# MAIN_MODULE.net
KiCad netlist of a schematic drawn in EAGLE
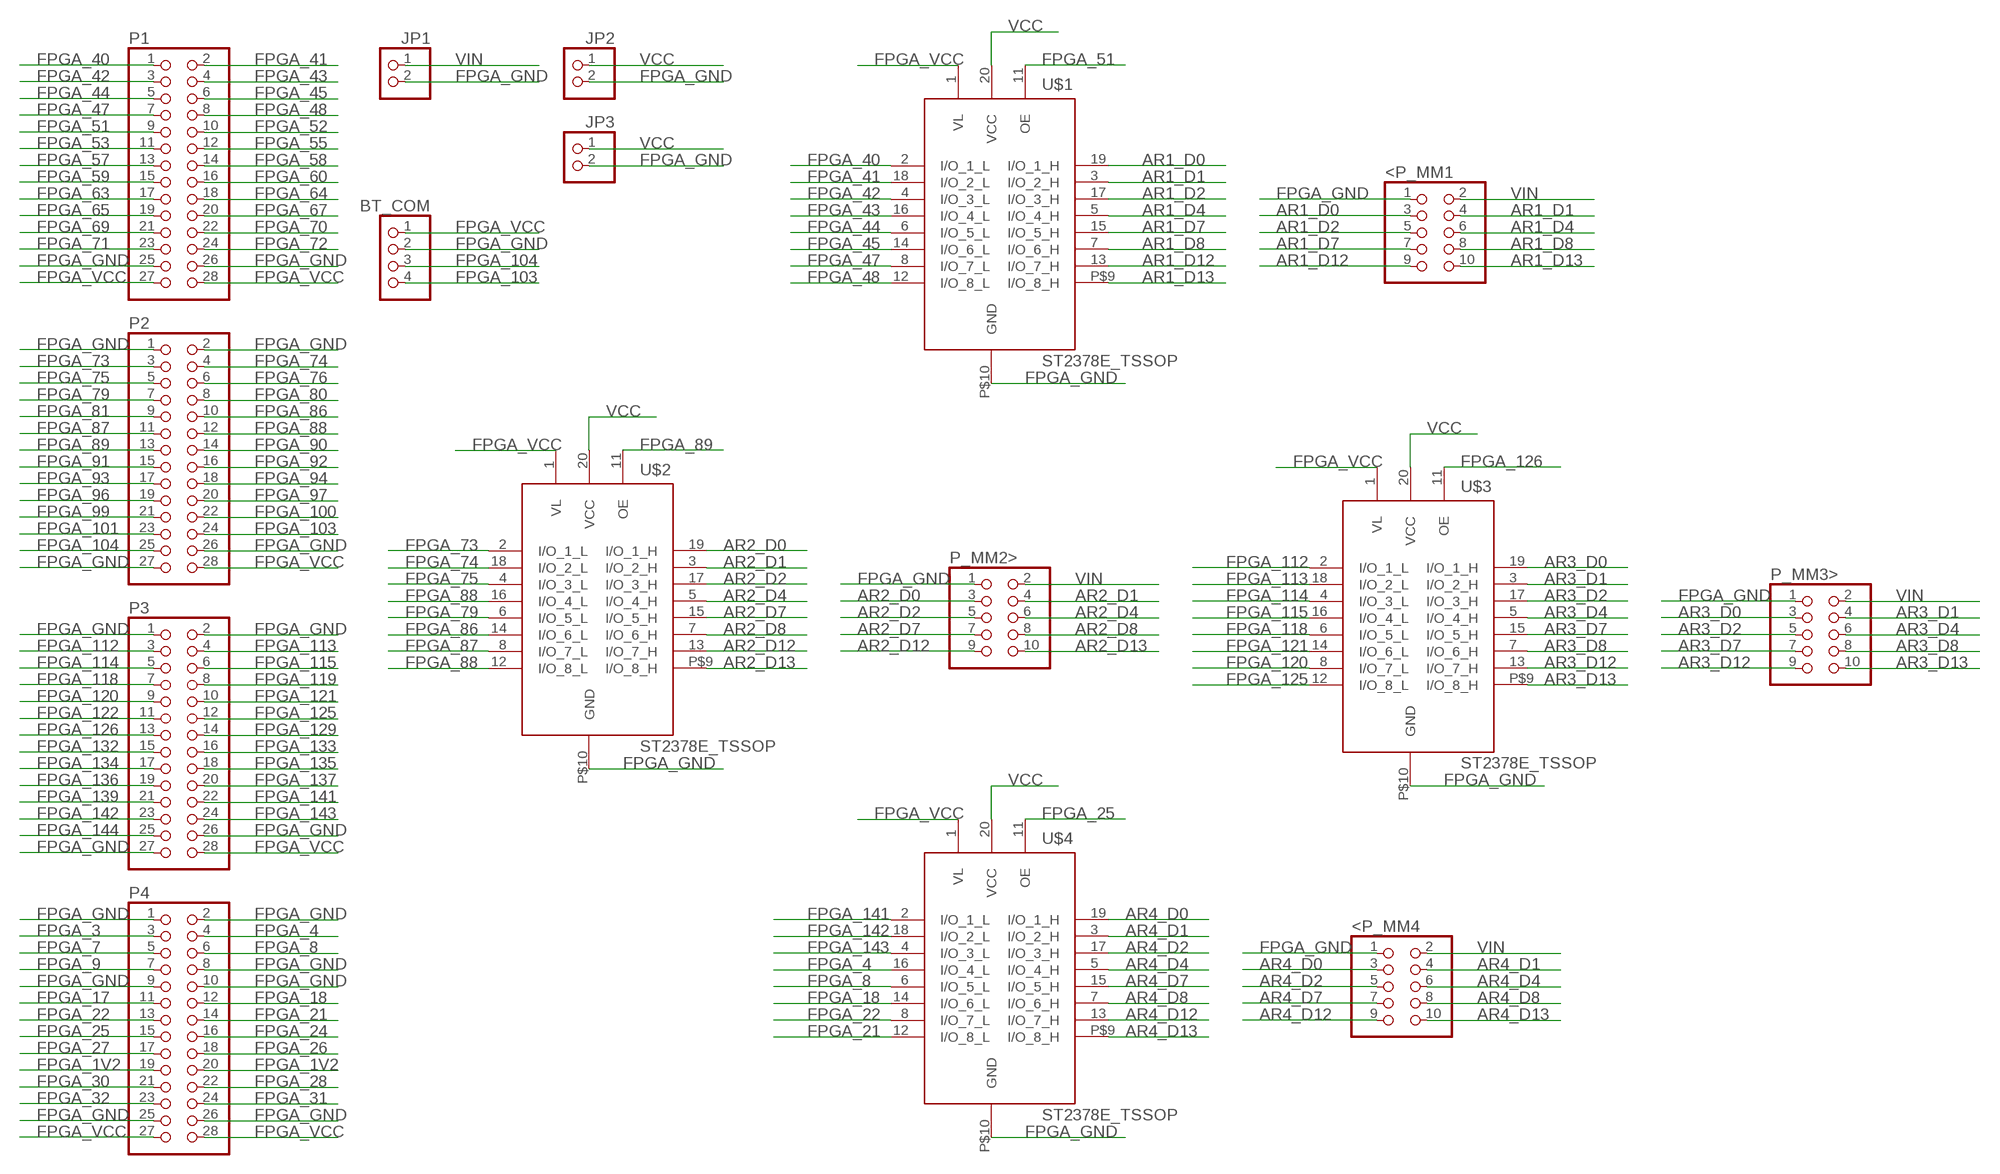
[diagram p0: schematic, sheet 1]

(export (version "E")
  (design (tool "Eeschema 10.0.6"))
  (components
    (comp (ref "<P_MM1")
      (value "PINHD-2X5")
      (footprint "eagle-import:2X05")
      (libsource (lib "eagle-import") (part "PINHD-2X5"))
    )
    (comp (ref "<P_MM4")
      (value "PINHD-2X5")
      (footprint "eagle-import:2X05")
      (libsource (lib "eagle-import") (part "PINHD-2X5"))
    )
    (comp (ref "BT_COM")
      (value "PINHD-1X4")
      (footprint "eagle-import:1X04")
      (libsource (lib "eagle-import") (part "PINHD-1X4"))
    )
    (comp (ref "JP1")
      (value "PINHD-1X2")
      (footprint "eagle-import:1X02")
      (libsource (lib "eagle-import") (part "PINHD-1X2"))
    )
    (comp (ref "JP2")
      (value "PINHD-1X2")
      (footprint "eagle-import:1X02")
      (libsource (lib "eagle-import") (part "PINHD-1X2"))
    )
    (comp (ref "JP3")
      (value "PINHD-1X2")
      (footprint "eagle-import:1X02")
      (libsource (lib "eagle-import") (part "PINHD-1X2"))
    )
    (comp (ref "P1")
      (value "PINHD-2X14")
      (footprint "eagle-import:2X14")
      (libsource (lib "eagle-import") (part "PINHD-2X14"))
    )
    (comp (ref "P2")
      (value "PINHD-2X14")
      (footprint "eagle-import:2X14")
      (libsource (lib "eagle-import") (part "PINHD-2X14"))
    )
    (comp (ref "P3")
      (value "PINHD-2X14")
      (footprint "eagle-import:2X14")
      (libsource (lib "eagle-import") (part "PINHD-2X14"))
    )
    (comp (ref "P4")
      (value "PINHD-2X14")
      (footprint "eagle-import:2X14")
      (libsource (lib "eagle-import") (part "PINHD-2X14"))
    )
    (comp (ref "P_MM2>")
      (value "PINHD-2X5")
      (footprint "eagle-import:2X05")
      (libsource (lib "eagle-import") (part "PINHD-2X5"))
    )
    (comp (ref "P_MM3>")
      (value "PINHD-2X5")
      (footprint "eagle-import:2X05")
      (libsource (lib "eagle-import") (part "PINHD-2X5"))
    )
    (comp (ref "U$1")
      (value "ST2378E_TSSOP")
      (footprint "eagle-import:TSSOP20")
      (libsource (lib "eagle-import") (part "ST2378E_TSSOP"))
    )
    (comp (ref "U$2")
      (value "ST2378E_TSSOP")
      (footprint "eagle-import:TSSOP20")
      (libsource (lib "eagle-import") (part "ST2378E_TSSOP"))
    )
    (comp (ref "U$3")
      (value "ST2378E_TSSOP")
      (footprint "eagle-import:TSSOP20")
      (libsource (lib "eagle-import") (part "ST2378E_TSSOP"))
    )
    (comp (ref "U$4")
      (value "ST2378E_TSSOP")
      (footprint "eagle-import:TSSOP20")
      (libsource (lib "eagle-import") (part "ST2378E_TSSOP"))
    )
  )
  (nets
    (net (code "1") (name "/AR1_D0") (class "Default")
      (node (ref "<P_MM1") (pin "3") (pinfunction "3_3") (pintype "passive"))
      (node (ref "U$1") (pin "19") (pinfunction "I/O_1_H_19") (pintype "bidirectional"))
    )
    (net (code "2") (name "/AR1_D1") (class "Default")
      (node (ref "<P_MM1") (pin "4") (pinfunction "4_4") (pintype "passive"))
      (node (ref "U$1") (pin "3") (pinfunction "I/O_2_H_3") (pintype "bidirectional"))
    )
    (net (code "3") (name "/AR1_D2") (class "Default")
      (node (ref "<P_MM1") (pin "5") (pinfunction "5_5") (pintype "passive"))
      (node (ref "U$1") (pin "17") (pinfunction "I/O_3_H_17") (pintype "bidirectional"))
    )
    (net (code "4") (name "/AR1_D4") (class "Default")
      (node (ref "<P_MM1") (pin "6") (pinfunction "6_6") (pintype "passive"))
      (node (ref "U$1") (pin "5") (pinfunction "I/O_4_H_5") (pintype "bidirectional"))
    )
    (net (code "5") (name "/AR1_D7") (class "Default")
      (node (ref "<P_MM1") (pin "7") (pinfunction "7_7") (pintype "passive"))
      (node (ref "U$1") (pin "15") (pinfunction "I/O_5_H_15") (pintype "bidirectional"))
    )
    (net (code "6") (name "/AR1_D8") (class "Default")
      (node (ref "<P_MM1") (pin "8") (pinfunction "8_8") (pintype "passive"))
      (node (ref "U$1") (pin "7") (pinfunction "I/O_6_H_7") (pintype "bidirectional"))
    )
    (net (code "7") (name "/AR1_D12") (class "Default")
      (node (ref "<P_MM1") (pin "9") (pinfunction "9_9") (pintype "passive"))
      (node (ref "U$1") (pin "13") (pinfunction "I/O_7_H_13") (pintype "bidirectional"))
    )
    (net (code "8") (name "/AR1_D13") (class "Default")
      (node (ref "<P_MM1") (pin "10") (pinfunction "10_10") (pintype "passive"))
      (node (ref "U$1") (pin "P$9") (pinfunction "I/O_8_H_P$9") (pintype "bidirectional"))
    )
    (net (code "9") (name "/AR2_D0") (class "Default")
      (node (ref "P_MM2>") (pin "3") (pinfunction "3_3") (pintype "passive"))
      (node (ref "U$2") (pin "19") (pinfunction "I/O_1_H_19") (pintype "bidirectional"))
    )
    (net (code "10") (name "/AR2_D1") (class "Default")
      (node (ref "P_MM2>") (pin "4") (pinfunction "4_4") (pintype "passive"))
      (node (ref "U$2") (pin "3") (pinfunction "I/O_2_H_3") (pintype "bidirectional"))
    )
    (net (code "11") (name "/AR2_D2") (class "Default")
      (node (ref "P_MM2>") (pin "5") (pinfunction "5_5") (pintype "passive"))
      (node (ref "U$2") (pin "17") (pinfunction "I/O_3_H_17") (pintype "bidirectional"))
    )
    (net (code "12") (name "/AR2_D4") (class "Default")
      (node (ref "P_MM2>") (pin "6") (pinfunction "6_6") (pintype "passive"))
      (node (ref "U$2") (pin "5") (pinfunction "I/O_4_H_5") (pintype "bidirectional"))
    )
    (net (code "13") (name "/AR2_D7") (class "Default")
      (node (ref "P_MM2>") (pin "7") (pinfunction "7_7") (pintype "passive"))
      (node (ref "U$2") (pin "15") (pinfunction "I/O_5_H_15") (pintype "bidirectional"))
    )
    (net (code "14") (name "/AR2_D8") (class "Default")
      (node (ref "P_MM2>") (pin "8") (pinfunction "8_8") (pintype "passive"))
      (node (ref "U$2") (pin "7") (pinfunction "I/O_6_H_7") (pintype "bidirectional"))
    )
    (net (code "15") (name "/AR2_D12") (class "Default")
      (node (ref "P_MM2>") (pin "9") (pinfunction "9_9") (pintype "passive"))
      (node (ref "U$2") (pin "13") (pinfunction "I/O_7_H_13") (pintype "bidirectional"))
    )
    (net (code "16") (name "/AR2_D13") (class "Default")
      (node (ref "P_MM2>") (pin "10") (pinfunction "10_10") (pintype "passive"))
      (node (ref "U$2") (pin "P$9") (pinfunction "I/O_8_H_P$9") (pintype "bidirectional"))
    )
    (net (code "17") (name "/AR3_D0") (class "Default")
      (node (ref "P_MM3>") (pin "3") (pinfunction "3_3") (pintype "passive"))
      (node (ref "U$3") (pin "19") (pinfunction "I/O_1_H_19") (pintype "bidirectional"))
    )
    (net (code "18") (name "/AR3_D1") (class "Default")
      (node (ref "P_MM3>") (pin "4") (pinfunction "4_4") (pintype "passive"))
      (node (ref "U$3") (pin "3") (pinfunction "I/O_2_H_3") (pintype "bidirectional"))
    )
    (net (code "19") (name "/AR3_D2") (class "Default")
      (node (ref "P_MM3>") (pin "5") (pinfunction "5_5") (pintype "passive"))
      (node (ref "U$3") (pin "17") (pinfunction "I/O_3_H_17") (pintype "bidirectional"))
    )
    (net (code "20") (name "/AR3_D4") (class "Default")
      (node (ref "P_MM3>") (pin "6") (pinfunction "6_6") (pintype "passive"))
      (node (ref "U$3") (pin "5") (pinfunction "I/O_4_H_5") (pintype "bidirectional"))
    )
    (net (code "21") (name "/AR3_D7") (class "Default")
      (node (ref "P_MM3>") (pin "7") (pinfunction "7_7") (pintype "passive"))
      (node (ref "U$3") (pin "15") (pinfunction "I/O_5_H_15") (pintype "bidirectional"))
    )
    (net (code "22") (name "/AR3_D8") (class "Default")
      (node (ref "P_MM3>") (pin "8") (pinfunction "8_8") (pintype "passive"))
      (node (ref "U$3") (pin "7") (pinfunction "I/O_6_H_7") (pintype "bidirectional"))
    )
    (net (code "23") (name "/AR3_D12") (class "Default")
      (node (ref "P_MM3>") (pin "9") (pinfunction "9_9") (pintype "passive"))
      (node (ref "U$3") (pin "13") (pinfunction "I/O_7_H_13") (pintype "bidirectional"))
    )
    (net (code "24") (name "/AR3_D13") (class "Default")
      (node (ref "P_MM3>") (pin "10") (pinfunction "10_10") (pintype "passive"))
      (node (ref "U$3") (pin "P$9") (pinfunction "I/O_8_H_P$9") (pintype "bidirectional"))
    )
    (net (code "25") (name "/AR4_D0") (class "Default")
      (node (ref "<P_MM4") (pin "3") (pinfunction "3_3") (pintype "passive"))
      (node (ref "U$4") (pin "19") (pinfunction "I/O_1_H_19") (pintype "bidirectional"))
    )
    (net (code "26") (name "/AR4_D1") (class "Default")
      (node (ref "<P_MM4") (pin "4") (pinfunction "4_4") (pintype "passive"))
      (node (ref "U$4") (pin "3") (pinfunction "I/O_2_H_3") (pintype "bidirectional"))
    )
    (net (code "27") (name "/AR4_D2") (class "Default")
      (node (ref "<P_MM4") (pin "5") (pinfunction "5_5") (pintype "passive"))
      (node (ref "U$4") (pin "17") (pinfunction "I/O_3_H_17") (pintype "bidirectional"))
    )
    (net (code "28") (name "/AR4_D4") (class "Default")
      (node (ref "<P_MM4") (pin "6") (pinfunction "6_6") (pintype "passive"))
      (node (ref "U$4") (pin "5") (pinfunction "I/O_4_H_5") (pintype "bidirectional"))
    )
    (net (code "29") (name "/AR4_D7") (class "Default")
      (node (ref "<P_MM4") (pin "7") (pinfunction "7_7") (pintype "passive"))
      (node (ref "U$4") (pin "15") (pinfunction "I/O_5_H_15") (pintype "bidirectional"))
    )
    (net (code "30") (name "/AR4_D8") (class "Default")
      (node (ref "<P_MM4") (pin "8") (pinfunction "8_8") (pintype "passive"))
      (node (ref "U$4") (pin "7") (pinfunction "I/O_6_H_7") (pintype "bidirectional"))
    )
    (net (code "31") (name "/AR4_D12") (class "Default")
      (node (ref "<P_MM4") (pin "9") (pinfunction "9_9") (pintype "passive"))
      (node (ref "U$4") (pin "13") (pinfunction "I/O_7_H_13") (pintype "bidirectional"))
    )
    (net (code "32") (name "/AR4_D13") (class "Default")
      (node (ref "<P_MM4") (pin "10") (pinfunction "10_10") (pintype "passive"))
      (node (ref "U$4") (pin "P$9") (pinfunction "I/O_8_H_P$9") (pintype "bidirectional"))
    )
    (net (code "33") (name "/FPGA_1V2") (class "Default")
      (node (ref "P4") (pin "19") (pinfunction "19_19") (pintype "passive"))
      (node (ref "P4") (pin "20") (pinfunction "20_20") (pintype "passive"))
    )
    (net (code "34") (name "/FPGA_3") (class "Default")
      (node (ref "P4") (pin "3") (pinfunction "3_3") (pintype "passive"))
    )
    (net (code "35") (name "/FPGA_4") (class "Default")
      (node (ref "P4") (pin "4") (pinfunction "4_4") (pintype "passive"))
      (node (ref "U$4") (pin "16") (pinfunction "I/O_4_L_16") (pintype "bidirectional"))
    )
    (net (code "36") (name "/FPGA_7") (class "Default")
      (node (ref "P4") (pin "5") (pinfunction "5_5") (pintype "passive"))
    )
    (net (code "37") (name "/FPGA_8") (class "Default")
      (node (ref "P4") (pin "6") (pinfunction "6_6") (pintype "passive"))
      (node (ref "U$4") (pin "6") (pinfunction "I/O_5_L_6") (pintype "bidirectional"))
    )
    (net (code "38") (name "/FPGA_9") (class "Default")
      (node (ref "P4") (pin "7") (pinfunction "7_7") (pintype "passive"))
    )
    (net (code "39") (name "/FPGA_17") (class "Default")
      (node (ref "P4") (pin "11") (pinfunction "11_11") (pintype "passive"))
    )
    (net (code "40") (name "/FPGA_18") (class "Default")
      (node (ref "P4") (pin "12") (pinfunction "12_12") (pintype "passive"))
      (node (ref "U$4") (pin "14") (pinfunction "I/O_6_L_14") (pintype "bidirectional"))
    )
    (net (code "41") (name "/FPGA_21") (class "Default")
      (node (ref "P4") (pin "14") (pinfunction "14_14") (pintype "passive"))
      (node (ref "U$4") (pin "12") (pinfunction "I/O_8_L_12") (pintype "bidirectional"))
    )
    (net (code "42") (name "/FPGA_22") (class "Default")
      (node (ref "P4") (pin "13") (pinfunction "13_13") (pintype "passive"))
      (node (ref "U$4") (pin "8") (pinfunction "I/O_7_L_8") (pintype "bidirectional"))
    )
    (net (code "43") (name "/FPGA_24") (class "Default")
      (node (ref "P4") (pin "16") (pinfunction "16_16") (pintype "passive"))
    )
    (net (code "44") (name "/FPGA_25") (class "Default")
      (node (ref "P4") (pin "15") (pinfunction "15_15") (pintype "passive"))
      (node (ref "U$4") (pin "11") (pinfunction "OE_11") (pintype "bidirectional"))
    )
    (net (code "45") (name "/FPGA_26") (class "Default")
      (node (ref "P4") (pin "18") (pinfunction "18_18") (pintype "passive"))
    )
    (net (code "46") (name "/FPGA_27") (class "Default")
      (node (ref "P4") (pin "17") (pinfunction "17_17") (pintype "passive"))
    )
    (net (code "47") (name "/FPGA_28") (class "Default")
      (node (ref "P4") (pin "22") (pinfunction "22_22") (pintype "passive"))
    )
    (net (code "48") (name "/FPGA_30") (class "Default")
      (node (ref "P4") (pin "21") (pinfunction "21_21") (pintype "passive"))
    )
    (net (code "49") (name "/FPGA_31") (class "Default")
      (node (ref "P4") (pin "24") (pinfunction "24_24") (pintype "passive"))
    )
    (net (code "50") (name "/FPGA_32") (class "Default")
      (node (ref "P4") (pin "23") (pinfunction "23_23") (pintype "passive"))
    )
    (net (code "51") (name "/FPGA_40") (class "Default")
      (node (ref "P1") (pin "1") (pinfunction "1_1") (pintype "passive"))
      (node (ref "U$1") (pin "2") (pinfunction "I/O_1_L_2") (pintype "bidirectional"))
    )
    (net (code "52") (name "/FPGA_41") (class "Default")
      (node (ref "P1") (pin "2") (pinfunction "2_2") (pintype "passive"))
      (node (ref "U$1") (pin "18") (pinfunction "I/O_2_L_18") (pintype "bidirectional"))
    )
    (net (code "53") (name "/FPGA_42") (class "Default")
      (node (ref "P1") (pin "3") (pinfunction "3_3") (pintype "passive"))
      (node (ref "U$1") (pin "4") (pinfunction "I/O_3_L_4") (pintype "bidirectional"))
    )
    (net (code "54") (name "/FPGA_43") (class "Default")
      (node (ref "P1") (pin "4") (pinfunction "4_4") (pintype "passive"))
      (node (ref "U$1") (pin "16") (pinfunction "I/O_4_L_16") (pintype "bidirectional"))
    )
    (net (code "55") (name "/FPGA_44") (class "Default")
      (node (ref "P1") (pin "5") (pinfunction "5_5") (pintype "passive"))
      (node (ref "U$1") (pin "6") (pinfunction "I/O_5_L_6") (pintype "bidirectional"))
    )
    (net (code "56") (name "/FPGA_45") (class "Default")
      (node (ref "P1") (pin "6") (pinfunction "6_6") (pintype "passive"))
      (node (ref "U$1") (pin "14") (pinfunction "I/O_6_L_14") (pintype "bidirectional"))
    )
    (net (code "57") (name "/FPGA_47") (class "Default")
      (node (ref "P1") (pin "7") (pinfunction "7_7") (pintype "passive"))
      (node (ref "U$1") (pin "8") (pinfunction "I/O_7_L_8") (pintype "bidirectional"))
    )
    (net (code "58") (name "/FPGA_48") (class "Default")
      (node (ref "P1") (pin "8") (pinfunction "8_8") (pintype "passive"))
      (node (ref "U$1") (pin "12") (pinfunction "I/O_8_L_12") (pintype "bidirectional"))
    )
    (net (code "59") (name "/FPGA_51") (class "Default")
      (node (ref "P1") (pin "9") (pinfunction "9_9") (pintype "passive"))
      (node (ref "U$1") (pin "11") (pinfunction "OE_11") (pintype "bidirectional"))
    )
    (net (code "60") (name "/FPGA_52") (class "Default")
      (node (ref "P1") (pin "10") (pinfunction "10_10") (pintype "passive"))
    )
    (net (code "61") (name "/FPGA_53") (class "Default")
      (node (ref "P1") (pin "11") (pinfunction "11_11") (pintype "passive"))
    )
    (net (code "62") (name "/FPGA_55") (class "Default")
      (node (ref "P1") (pin "12") (pinfunction "12_12") (pintype "passive"))
    )
    (net (code "63") (name "/FPGA_57") (class "Default")
      (node (ref "P1") (pin "13") (pinfunction "13_13") (pintype "passive"))
    )
    (net (code "64") (name "/FPGA_58") (class "Default")
      (node (ref "P1") (pin "14") (pinfunction "14_14") (pintype "passive"))
    )
    (net (code "65") (name "/FPGA_59") (class "Default")
      (node (ref "P1") (pin "15") (pinfunction "15_15") (pintype "passive"))
    )
    (net (code "66") (name "/FPGA_60") (class "Default")
      (node (ref "P1") (pin "16") (pinfunction "16_16") (pintype "passive"))
    )
    (net (code "67") (name "/FPGA_63") (class "Default")
      (node (ref "P1") (pin "17") (pinfunction "17_17") (pintype "passive"))
    )
    (net (code "68") (name "/FPGA_64") (class "Default")
      (node (ref "P1") (pin "18") (pinfunction "18_18") (pintype "passive"))
    )
    (net (code "69") (name "/FPGA_65") (class "Default")
      (node (ref "P1") (pin "19") (pinfunction "19_19") (pintype "passive"))
    )
    (net (code "70") (name "/FPGA_67") (class "Default")
      (node (ref "P1") (pin "20") (pinfunction "20_20") (pintype "passive"))
    )
    (net (code "71") (name "/FPGA_69") (class "Default")
      (node (ref "P1") (pin "21") (pinfunction "21_21") (pintype "passive"))
    )
    (net (code "72") (name "/FPGA_70") (class "Default")
      (node (ref "P1") (pin "22") (pinfunction "22_22") (pintype "passive"))
    )
    (net (code "73") (name "/FPGA_71") (class "Default")
      (node (ref "P1") (pin "23") (pinfunction "23_23") (pintype "passive"))
    )
    (net (code "74") (name "/FPGA_72") (class "Default")
      (node (ref "P1") (pin "24") (pinfunction "24_24") (pintype "passive"))
    )
    (net (code "75") (name "/FPGA_73") (class "Default")
      (node (ref "P2") (pin "3") (pinfunction "3_3") (pintype "passive"))
      (node (ref "U$2") (pin "2") (pinfunction "I/O_1_L_2") (pintype "bidirectional"))
    )
    (net (code "76") (name "/FPGA_74") (class "Default")
      (node (ref "P2") (pin "4") (pinfunction "4_4") (pintype "passive"))
      (node (ref "U$2") (pin "18") (pinfunction "I/O_2_L_18") (pintype "bidirectional"))
    )
    (net (code "77") (name "/FPGA_75") (class "Default")
      (node (ref "P2") (pin "5") (pinfunction "5_5") (pintype "passive"))
      (node (ref "U$2") (pin "4") (pinfunction "I/O_3_L_4") (pintype "bidirectional"))
    )
    (net (code "78") (name "/FPGA_76") (class "Default")
      (node (ref "P2") (pin "6") (pinfunction "6_6") (pintype "passive"))
    )
    (net (code "79") (name "/FPGA_79") (class "Default")
      (node (ref "P2") (pin "7") (pinfunction "7_7") (pintype "passive"))
      (node (ref "U$2") (pin "6") (pinfunction "I/O_5_L_6") (pintype "bidirectional"))
    )
    (net (code "80") (name "/FPGA_80") (class "Default")
      (node (ref "P2") (pin "8") (pinfunction "8_8") (pintype "passive"))
    )
    (net (code "81") (name "/FPGA_81") (class "Default")
      (node (ref "P2") (pin "9") (pinfunction "9_9") (pintype "passive"))
    )
    (net (code "82") (name "/FPGA_86") (class "Default")
      (node (ref "P2") (pin "10") (pinfunction "10_10") (pintype "passive"))
      (node (ref "U$2") (pin "14") (pinfunction "I/O_6_L_14") (pintype "bidirectional"))
    )
    (net (code "83") (name "/FPGA_87") (class "Default")
      (node (ref "P2") (pin "11") (pinfunction "11_11") (pintype "passive"))
      (node (ref "U$2") (pin "8") (pinfunction "I/O_7_L_8") (pintype "bidirectional"))
    )
    (net (code "84") (name "/FPGA_88") (class "Default")
      (node (ref "P2") (pin "12") (pinfunction "12_12") (pintype "passive"))
      (node (ref "U$2") (pin "12") (pinfunction "I/O_8_L_12") (pintype "bidirectional"))
      (node (ref "U$2") (pin "16") (pinfunction "I/O_4_L_16") (pintype "bidirectional"))
    )
    (net (code "85") (name "/FPGA_89") (class "Default")
      (node (ref "P2") (pin "13") (pinfunction "13_13") (pintype "passive"))
      (node (ref "U$2") (pin "11") (pinfunction "OE_11") (pintype "bidirectional"))
    )
    (net (code "86") (name "/FPGA_90") (class "Default")
      (node (ref "P2") (pin "14") (pinfunction "14_14") (pintype "passive"))
    )
    (net (code "87") (name "/FPGA_91") (class "Default")
      (node (ref "P2") (pin "15") (pinfunction "15_15") (pintype "passive"))
    )
    (net (code "88") (name "/FPGA_92") (class "Default")
      (node (ref "P2") (pin "16") (pinfunction "16_16") (pintype "passive"))
    )
    (net (code "89") (name "/FPGA_93") (class "Default")
      (node (ref "P2") (pin "17") (pinfunction "17_17") (pintype "passive"))
    )
    (net (code "90") (name "/FPGA_94") (class "Default")
      (node (ref "P2") (pin "18") (pinfunction "18_18") (pintype "passive"))
    )
    (net (code "91") (name "/FPGA_96") (class "Default")
      (node (ref "P2") (pin "19") (pinfunction "19_19") (pintype "passive"))
    )
    (net (code "92") (name "/FPGA_97") (class "Default")
      (node (ref "P2") (pin "20") (pinfunction "20_20") (pintype "passive"))
    )
    (net (code "93") (name "/FPGA_99") (class "Default")
      (node (ref "P2") (pin "21") (pinfunction "21_21") (pintype "passive"))
    )
    (net (code "94") (name "/FPGA_100") (class "Default")
      (node (ref "P2") (pin "22") (pinfunction "22_22") (pintype "passive"))
    )
    (net (code "95") (name "/FPGA_101") (class "Default")
      (node (ref "P2") (pin "23") (pinfunction "23_23") (pintype "passive"))
    )
    (net (code "96") (name "/FPGA_103") (class "Default")
      (node (ref "BT_COM") (pin "4") (pinfunction "4_4") (pintype "passive"))
      (node (ref "P2") (pin "24") (pinfunction "24_24") (pintype "passive"))
    )
    (net (code "97") (name "/FPGA_104") (class "Default")
      (node (ref "BT_COM") (pin "3") (pinfunction "3_3") (pintype "passive"))
      (node (ref "P2") (pin "25") (pinfunction "25_25") (pintype "passive"))
    )
    (net (code "98") (name "/FPGA_112") (class "Default")
      (node (ref "P3") (pin "3") (pinfunction "3_3") (pintype "passive"))
      (node (ref "U$3") (pin "2") (pinfunction "I/O_1_L_2") (pintype "bidirectional"))
    )
    (net (code "99") (name "/FPGA_113") (class "Default")
      (node (ref "P3") (pin "4") (pinfunction "4_4") (pintype "passive"))
      (node (ref "U$3") (pin "18") (pinfunction "I/O_2_L_18") (pintype "bidirectional"))
    )
    (net (code "100") (name "/FPGA_114") (class "Default")
      (node (ref "P3") (pin "5") (pinfunction "5_5") (pintype "passive"))
      (node (ref "U$3") (pin "4") (pinfunction "I/O_3_L_4") (pintype "bidirectional"))
    )
    (net (code "101") (name "/FPGA_115") (class "Default")
      (node (ref "P3") (pin "6") (pinfunction "6_6") (pintype "passive"))
      (node (ref "U$3") (pin "16") (pinfunction "I/O_4_L_16") (pintype "bidirectional"))
    )
    (net (code "102") (name "/FPGA_118") (class "Default")
      (node (ref "P3") (pin "7") (pinfunction "7_7") (pintype "passive"))
      (node (ref "U$3") (pin "6") (pinfunction "I/O_5_L_6") (pintype "bidirectional"))
    )
    (net (code "103") (name "/FPGA_119") (class "Default")
      (node (ref "P3") (pin "8") (pinfunction "8_8") (pintype "passive"))
    )
    (net (code "104") (name "/FPGA_120") (class "Default")
      (node (ref "P3") (pin "9") (pinfunction "9_9") (pintype "passive"))
      (node (ref "U$3") (pin "8") (pinfunction "I/O_7_L_8") (pintype "bidirectional"))
    )
    (net (code "105") (name "/FPGA_121") (class "Default")
      (node (ref "P3") (pin "10") (pinfunction "10_10") (pintype "passive"))
      (node (ref "U$3") (pin "14") (pinfunction "I/O_6_L_14") (pintype "bidirectional"))
    )
    (net (code "106") (name "/FPGA_122") (class "Default")
      (node (ref "P3") (pin "11") (pinfunction "11_11") (pintype "passive"))
    )
    (net (code "107") (name "/FPGA_125") (class "Default")
      (node (ref "P3") (pin "12") (pinfunction "12_12") (pintype "passive"))
      (node (ref "U$3") (pin "12") (pinfunction "I/O_8_L_12") (pintype "bidirectional"))
    )
    (net (code "108") (name "/FPGA_126") (class "Default")
      (node (ref "P3") (pin "13") (pinfunction "13_13") (pintype "passive"))
      (node (ref "U$3") (pin "11") (pinfunction "OE_11") (pintype "bidirectional"))
    )
    (net (code "109") (name "/FPGA_129") (class "Default")
      (node (ref "P3") (pin "14") (pinfunction "14_14") (pintype "passive"))
    )
    (net (code "110") (name "/FPGA_132") (class "Default")
      (node (ref "P3") (pin "15") (pinfunction "15_15") (pintype "passive"))
    )
    (net (code "111") (name "/FPGA_133") (class "Default")
      (node (ref "P3") (pin "16") (pinfunction "16_16") (pintype "passive"))
    )
    (net (code "112") (name "/FPGA_134") (class "Default")
      (node (ref "P3") (pin "17") (pinfunction "17_17") (pintype "passive"))
    )
    (net (code "113") (name "/FPGA_135") (class "Default")
      (node (ref "P3") (pin "18") (pinfunction "18_18") (pintype "passive"))
    )
    (net (code "114") (name "/FPGA_136") (class "Default")
      (node (ref "P3") (pin "19") (pinfunction "19_19") (pintype "passive"))
    )
    (net (code "115") (name "/FPGA_137") (class "Default")
      (node (ref "P3") (pin "20") (pinfunction "20_20") (pintype "passive"))
    )
    (net (code "116") (name "/FPGA_139") (class "Default")
      (node (ref "P3") (pin "21") (pinfunction "21_21") (pintype "passive"))
    )
    (net (code "117") (name "/FPGA_141") (class "Default")
      (node (ref "P3") (pin "22") (pinfunction "22_22") (pintype "passive"))
      (node (ref "U$4") (pin "2") (pinfunction "I/O_1_L_2") (pintype "bidirectional"))
    )
    (net (code "118") (name "/FPGA_142") (class "Default")
      (node (ref "P3") (pin "23") (pinfunction "23_23") (pintype "passive"))
      (node (ref "U$4") (pin "18") (pinfunction "I/O_2_L_18") (pintype "bidirectional"))
    )
    (net (code "119") (name "/FPGA_143") (class "Default")
      (node (ref "P3") (pin "24") (pinfunction "24_24") (pintype "passive"))
      (node (ref "U$4") (pin "4") (pinfunction "I/O_3_L_4") (pintype "bidirectional"))
    )
    (net (code "120") (name "/FPGA_144") (class "Default")
      (node (ref "P3") (pin "25") (pinfunction "25_25") (pintype "passive"))
    )
    (net (code "121") (name "/FPGA_GND") (class "Default")
      (node (ref "<P_MM1") (pin "1") (pinfunction "1_1") (pintype "passive"))
      (node (ref "<P_MM4") (pin "1") (pinfunction "1_1") (pintype "passive"))
      (node (ref "BT_COM") (pin "2") (pinfunction "2_2") (pintype "passive"))
      (node (ref "JP1") (pin "2") (pinfunction "2_2") (pintype "passive"))
      (node (ref "JP2") (pin "2") (pinfunction "2_2") (pintype "passive"))
      (node (ref "JP3") (pin "2") (pinfunction "2_2") (pintype "passive"))
      (node (ref "P1") (pin "25") (pinfunction "25_25") (pintype "passive"))
      (node (ref "P1") (pin "26") (pinfunction "26_26") (pintype "passive"))
      (node (ref "P2") (pin "1") (pinfunction "1_1") (pintype "passive"))
      (node (ref "P2") (pin "2") (pinfunction "2_2") (pintype "passive"))
      (node (ref "P2") (pin "26") (pinfunction "26_26") (pintype "passive"))
      (node (ref "P2") (pin "27") (pinfunction "27_27") (pintype "passive"))
      (node (ref "P3") (pin "1") (pinfunction "1_1") (pintype "passive"))
      (node (ref "P3") (pin "2") (pinfunction "2_2") (pintype "passive"))
      (node (ref "P3") (pin "26") (pinfunction "26_26") (pintype "passive"))
      (node (ref "P3") (pin "27") (pinfunction "27_27") (pintype "passive"))
      (node (ref "P4") (pin "1") (pinfunction "1_1") (pintype "passive"))
      (node (ref "P4") (pin "10") (pinfunction "10_10") (pintype "passive"))
      (node (ref "P4") (pin "2") (pinfunction "2_2") (pintype "passive"))
      (node (ref "P4") (pin "25") (pinfunction "25_25") (pintype "passive"))
      (node (ref "P4") (pin "26") (pinfunction "26_26") (pintype "passive"))
      (node (ref "P4") (pin "8") (pinfunction "8_8") (pintype "passive"))
      (node (ref "P4") (pin "9") (pinfunction "9_9") (pintype "passive"))
      (node (ref "P_MM2>") (pin "1") (pinfunction "1_1") (pintype "passive"))
      (node (ref "P_MM3>") (pin "1") (pinfunction "1_1") (pintype "passive"))
      (node (ref "U$1") (pin "P$10") (pinfunction "GND_P$10") (pintype "bidirectional"))
      (node (ref "U$2") (pin "P$10") (pinfunction "GND_P$10") (pintype "bidirectional"))
      (node (ref "U$3") (pin "P$10") (pinfunction "GND_P$10") (pintype "bidirectional"))
      (node (ref "U$4") (pin "P$10") (pinfunction "GND_P$10") (pintype "bidirectional"))
    )
    (net (code "122") (name "/FPGA_VCC") (class "Default")
      (node (ref "BT_COM") (pin "1") (pinfunction "1_1") (pintype "passive"))
      (node (ref "P1") (pin "27") (pinfunction "27_27") (pintype "passive"))
      (node (ref "P1") (pin "28") (pinfunction "28_28") (pintype "passive"))
      (node (ref "P2") (pin "28") (pinfunction "28_28") (pintype "passive"))
      (node (ref "P3") (pin "28") (pinfunction "28_28") (pintype "passive"))
      (node (ref "P4") (pin "27") (pinfunction "27_27") (pintype "passive"))
      (node (ref "P4") (pin "28") (pinfunction "28_28") (pintype "passive"))
      (node (ref "U$1") (pin "1") (pinfunction "VL_1") (pintype "bidirectional"))
      (node (ref "U$2") (pin "1") (pinfunction "VL_1") (pintype "bidirectional"))
      (node (ref "U$3") (pin "1") (pinfunction "VL_1") (pintype "bidirectional"))
      (node (ref "U$4") (pin "1") (pinfunction "VL_1") (pintype "bidirectional"))
    )
    (net (code "123") (name "/VCC") (class "Default")
      (node (ref "JP2") (pin "1") (pinfunction "1_1") (pintype "passive"))
      (node (ref "JP3") (pin "1") (pinfunction "1_1") (pintype "passive"))
      (node (ref "U$1") (pin "20") (pinfunction "VCC_20") (pintype "bidirectional"))
      (node (ref "U$2") (pin "20") (pinfunction "VCC_20") (pintype "bidirectional"))
      (node (ref "U$3") (pin "20") (pinfunction "VCC_20") (pintype "bidirectional"))
      (node (ref "U$4") (pin "20") (pinfunction "VCC_20") (pintype "bidirectional"))
    )
    (net (code "124") (name "/VIN") (class "Default")
      (node (ref "<P_MM1") (pin "2") (pinfunction "2_2") (pintype "passive"))
      (node (ref "<P_MM4") (pin "2") (pinfunction "2_2") (pintype "passive"))
      (node (ref "JP1") (pin "1") (pinfunction "1_1") (pintype "passive"))
      (node (ref "P_MM2>") (pin "2") (pinfunction "2_2") (pintype "passive"))
      (node (ref "P_MM3>") (pin "2") (pinfunction "2_2") (pintype "passive"))
    )
  )
)
